# mcu.net
KiCad netlist of a schematic drawn in Altium Designer
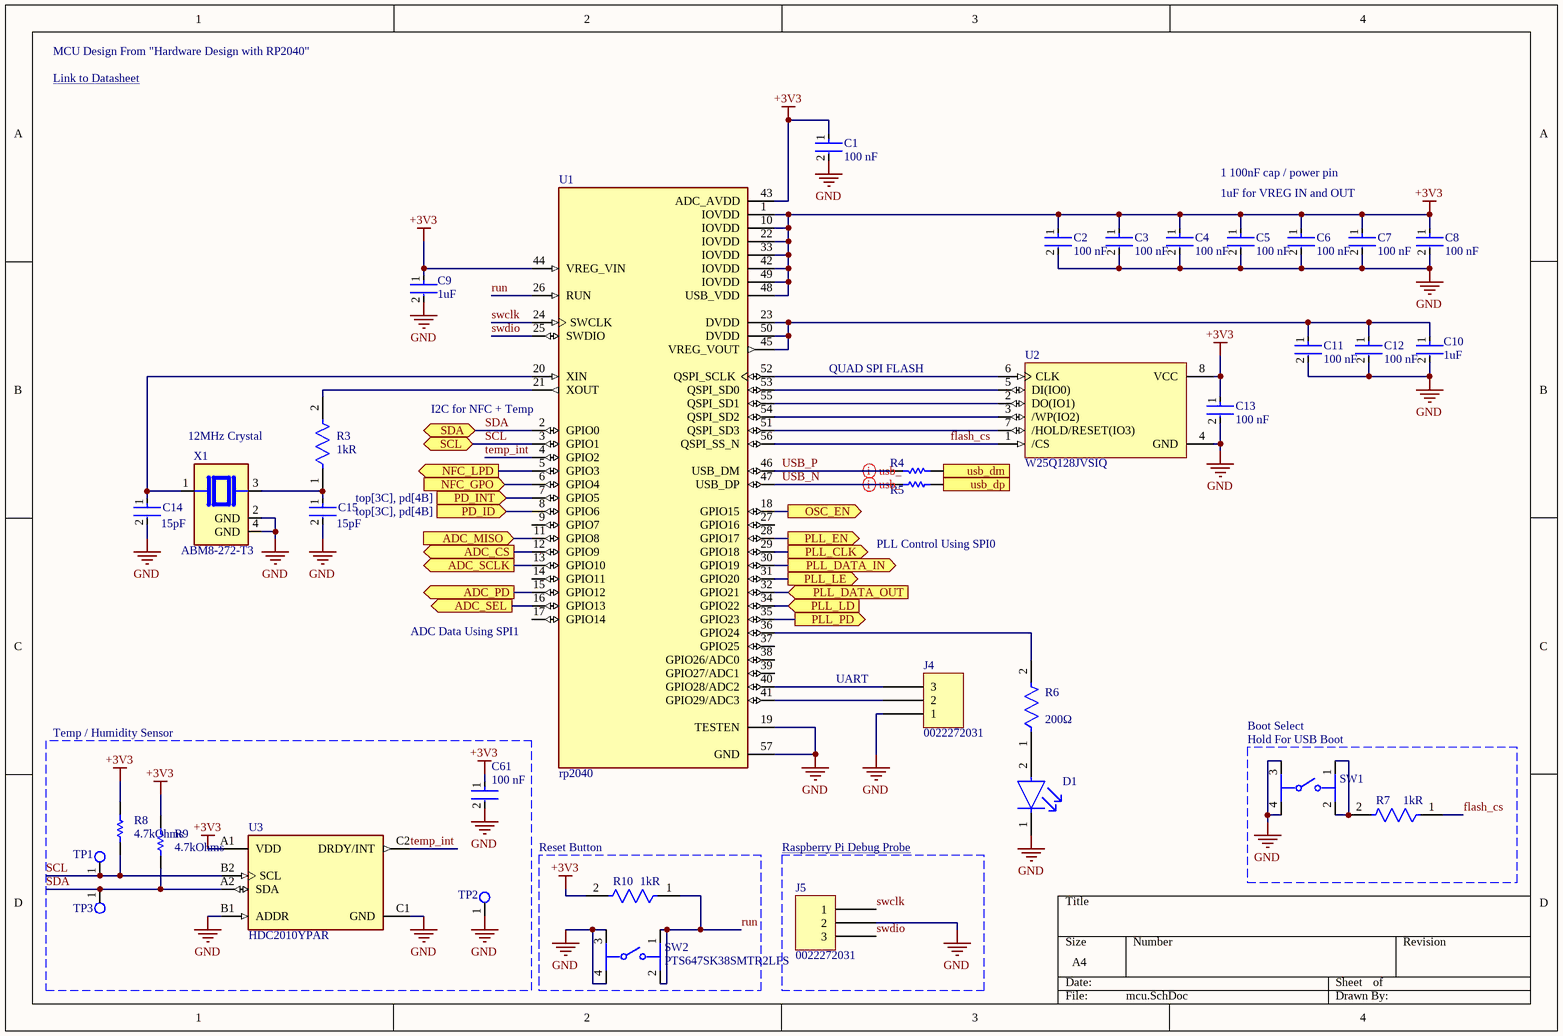
[diagram p0: mcu.SchDoc]

(export (version "E")
  (design (tool "Eeschema 10.0.6"))
  (components
    (comp (ref "C1")
      (value "CC0603KRX7R7BB104")
      (footprint "FP-CC0603-DA-MFG")
      (description "CAP CER 0.1UF 16V X7R 0603")
      (fields
        (field (name "OCTOPART") "https://octopart.com/cc0603krx7r7bb104-yageo-192941")
        (field (name "TOLERANCE") "0.1")
        (field (name "CAPACITANCE") "100 nF")
      )
      (libsource (lib "Altium Content Vault") (part "11868f565c42a9108669ba33697ecf6"))
    )
    (comp (ref "C2")
      (value "CC0603KRX7R7BB104")
      (footprint "FP-CC0603-DA-MFG")
      (description "CAP CER 0.1UF 16V X7R 0603")
      (fields
        (field (name "OCTOPART") "https://octopart.com/cc0603krx7r7bb104-yageo-192941")
        (field (name "TOLERANCE") "0.1")
        (field (name "CAPACITANCE") "100 nF")
      )
      (libsource (lib "Altium Content Vault") (part "11868f565c42a9108669ba33697ecf6"))
    )
    (comp (ref "C3")
      (value "CC0603KRX7R7BB104")
      (footprint "FP-CC0603-DA-MFG")
      (description "CAP CER 0.1UF 16V X7R 0603")
      (fields
        (field (name "OCTOPART") "https://octopart.com/cc0603krx7r7bb104-yageo-192941")
        (field (name "TOLERANCE") "0.1")
        (field (name "CAPACITANCE") "100 nF")
      )
      (libsource (lib "Altium Content Vault") (part "11868f565c42a9108669ba33697ecf6"))
    )
    (comp (ref "C4")
      (value "CC0603KRX7R7BB104")
      (footprint "FP-CC0603-DA-MFG")
      (description "CAP CER 0.1UF 16V X7R 0603")
      (fields
        (field (name "OCTOPART") "https://octopart.com/cc0603krx7r7bb104-yageo-192941")
        (field (name "TOLERANCE") "0.1")
        (field (name "CAPACITANCE") "100 nF")
      )
      (libsource (lib "Altium Content Vault") (part "11868f565c42a9108669ba33697ecf6"))
    )
    (comp (ref "C5")
      (value "CC0603KRX7R7BB104")
      (footprint "FP-CC0603-DA-MFG")
      (description "CAP CER 0.1UF 16V X7R 0603")
      (fields
        (field (name "OCTOPART") "https://octopart.com/cc0603krx7r7bb104-yageo-192941")
        (field (name "TOLERANCE") "0.1")
        (field (name "CAPACITANCE") "100 nF")
      )
      (libsource (lib "Altium Content Vault") (part "11868f565c42a9108669ba33697ecf6"))
    )
    (comp (ref "C6")
      (value "CC0603KRX7R7BB104")
      (footprint "FP-CC0603-DA-MFG")
      (description "CAP CER 0.1UF 16V X7R 0603")
      (fields
        (field (name "OCTOPART") "https://octopart.com/cc0603krx7r7bb104-yageo-192941")
        (field (name "TOLERANCE") "0.1")
        (field (name "CAPACITANCE") "100 nF")
      )
      (libsource (lib "Altium Content Vault") (part "11868f565c42a9108669ba33697ecf6"))
    )
    (comp (ref "C7")
      (value "CC0603KRX7R7BB104")
      (footprint "FP-CC0603-DA-MFG")
      (description "CAP CER 0.1UF 16V X7R 0603")
      (fields
        (field (name "OCTOPART") "https://octopart.com/cc0603krx7r7bb104-yageo-192941")
        (field (name "TOLERANCE") "0.1")
        (field (name "CAPACITANCE") "100 nF")
      )
      (libsource (lib "Altium Content Vault") (part "11868f565c42a9108669ba33697ecf6"))
    )
    (comp (ref "C8")
      (value "CC0603KRX7R7BB104")
      (footprint "FP-CC0603-DA-MFG")
      (description "CAP CER 0.1UF 16V X7R 0603")
      (fields
        (field (name "OCTOPART") "https://octopart.com/cc0603krx7r7bb104-yageo-192941")
        (field (name "TOLERANCE") "0.1")
        (field (name "CAPACITANCE") "100 nF")
      )
      (libsource (lib "Altium Content Vault") (part "11868f565c42a9108669ba33697ecf6"))
    )
    (comp (ref "C9")
      (value "CL10B105KP8NNNC")
      (footprint "FP-CL10-IPC_C")
      (description "Cap Ceramic 1uF 10V X7R ±10% Pad SMD 0603 +125°C T/R")
      (fields (field (name "CAPACITANCE") "1uF") (field (name "TOLERANCE") "10%"))
      (libsource (lib "Altium Content Vault") (part "b4654b650e69147ec39a6b967a45e02"))
    )
    (comp (ref "C10")
      (value "CL10B105KP8NNNC")
      (footprint "FP-CL10-IPC_C")
      (description "Cap Ceramic 1uF 10V X7R ±10% Pad SMD 0603 +125°C T/R")
      (fields (field (name "CAPACITANCE") "1uF") (field (name "TOLERANCE") "10%"))
      (libsource (lib "Altium Content Vault") (part "b4654b650e69147ec39a6b967a45e02"))
    )
    (comp (ref "C11")
      (value "CC0603KRX7R7BB104")
      (footprint "FP-CC0603-DA-MFG")
      (description "CAP CER 0.1UF 16V X7R 0603")
      (fields
        (field (name "OCTOPART") "https://octopart.com/cc0603krx7r7bb104-yageo-192941")
        (field (name "TOLERANCE") "0.1")
        (field (name "CAPACITANCE") "100 nF")
      )
      (libsource (lib "Altium Content Vault") (part "11868f565c42a9108669ba33697ecf6"))
    )
    (comp (ref "C12")
      (value "CC0603KRX7R7BB104")
      (footprint "FP-CC0603-DA-MFG")
      (description "CAP CER 0.1UF 16V X7R 0603")
      (fields
        (field (name "OCTOPART") "https://octopart.com/cc0603krx7r7bb104-yageo-192941")
        (field (name "TOLERANCE") "0.1")
        (field (name "CAPACITANCE") "100 nF")
      )
      (libsource (lib "Altium Content Vault") (part "11868f565c42a9108669ba33697ecf6"))
    )
    (comp (ref "C13")
      (value "CC0603KRX7R7BB104")
      (footprint "FP-CC0603-DA-MFG")
      (description "CAP CER 0.1UF 16V X7R 0603")
      (fields
        (field (name "OCTOPART") "https://octopart.com/cc0603krx7r7bb104-yageo-192941")
        (field (name "TOLERANCE") "0.1")
        (field (name "CAPACITANCE") "100 nF")
      )
      (libsource (lib "Altium Content Vault") (part "11868f565c42a9108669ba33697ecf6"))
    )
    (comp (ref "C14")
      (value "GJM1555C1H150GB01D")
      (footprint "FP-GJM155-0_05-MFG")
      (description "Multi-Layer Ceramic Capacitor 15pF C0G  ±2% 0402 Paper T/R")
      (fields (field (name "CAPACITANCE") "15pF") (field (name "TOLERANCE") "2%"))
      (libsource (lib "Altium Content Vault") (part "02cd4be3c70576c341d710602a673aa"))
    )
    (comp (ref "C15")
      (value "GJM1555C1H150GB01D")
      (footprint "FP-GJM155-0_05-MFG")
      (description "Multi-Layer Ceramic Capacitor 15pF C0G  ±2% 0402 Paper T/R")
      (fields (field (name "CAPACITANCE") "15pF") (field (name "TOLERANCE") "2%"))
      (libsource (lib "Altium Content Vault") (part "02cd4be3c70576c341d710602a673aa"))
    )
    (comp (ref "C61")
      (value "CC0603KRX7R7BB104")
      (footprint "FP-CC0603-DA-MFG")
      (description "CAP CER 0.1UF 16V X7R 0603")
      (fields
        (field (name "OCTOPART") "https://octopart.com/cc0603krx7r7bb104-yageo-192941")
        (field (name "TOLERANCE") "0.1")
        (field (name "CAPACITANCE") "100 nF")
      )
      (libsource (lib "Altium Content Vault") (part "11868f565c42a9108669ba33697ecf6"))
    )
    (comp (ref "D1")
      (value "LTST-C190KRKT")
      (footprint "FP-LTST-C190KRKT-MFG")
      (description "LED RED CLEAR CHIP SMD")
      (libsource (lib "Altium Content Vault") (part "8706943c75ba83719d021d2fdc84c58"))
    )
    (comp (ref "J4")
      (value "0022272031")
      (footprint "MOLEX KK 0022272031")
      (description "CONN HEADER VERT 3POS 2.54MM")
      (fields (field (name "MANUFACTURER") "Molex"))
      (libsource (lib "Celestial Altium Library - altium_library") (part "3 Pin"))
    )
    (comp (ref "J5")
      (value "0022272031")
      (footprint "MOLEX KK 0022272031")
      (description "CONN HEADER VERT 3POS 2.54MM")
      (fields (field (name "MANUFACTURER") "Molex"))
      (libsource (lib "") (part "3 Pin_1"))
    )
    (comp (ref "R3")
      (value "RC0603FR-071KL")
      (footprint "FP-RC0603-0_55-IPC_C")
      (description "RES 1K OHM 1% 1/10W 0603")
      (fields (field (name "RESISTANCE") "1kR") (field (name "TOLERANCE") "1%"))
      (libsource (lib "Altium Content Vault") (part "1029c3af85768c4190bb7ad29bc67b5"))
    )
    (comp (ref "R4")
      (value "RC0402JR-0727RL")
      (footprint "RESC1005X40X25NL05T10")
      (fields (field (name "MANUFACTURER") "Yageo / Phycomp"))
      (libsource (lib "Altium Content Vault") (part "RES"))
    )
    (comp (ref "R5")
      (value "RC0402JR-0727RL")
      (footprint "RESC1005X40X25NL05T10")
      (fields (field (name "MANUFACTURER") "Yageo / Phycomp"))
      (libsource (lib "Altium Content Vault") (part "RES"))
    )
    (comp (ref "R6")
      (value "200Ω")
      (footprint "FP-RT0402-MFG")
      (description "RES SMD 200 OHM 0.1% 1/16W 0402")
      (fields (field (name "TOLERANCE") "0.001") (field (name "MANUFACTURER PART NUMBER") "RT0402BRD07200RL"))
      (libsource (lib "Altium Content Vault") (part "1029c3af85768c4190bb7ad29bc67b5"))
    )
    (comp (ref "R7")
      (value "RC0603FR-071KL")
      (footprint "FP-RC0603-0_55-IPC_C")
      (description "RES 1K OHM 1% 1/10W 0603")
      (fields (field (name "RESISTANCE") "1kR") (field (name "TOLERANCE") "1%"))
      (libsource (lib "Altium Content Vault") (part "1029c3af85768c4190bb7ad29bc67b5"))
    )
    (comp (ref "R8")
      (value "RC0603FR-074K7L")
      (footprint "RESC1608X55X25LL10T15")
      (description "Chip Resistor, 4.7 KOhm, +/- 1%, 0.1 W, -55 to 155 degC, 0603 (1608 Metric), RoHS, Tape and Reel")
      (fields
        (field (name "MANUFACTURER") "Yageo")
        (field (name "RESISTANCE") "4.7kOhms")
        (field (name "TOLERANCE") "1%")
      )
      (libsource (lib "Altium Content Vault") (part "RES-2"))
    )
    (comp (ref "R9")
      (value "RC0603FR-074K7L")
      (footprint "RESC1608X55X25LL10T15")
      (description "Chip Resistor, 4.7 KOhm, +/- 1%, 0.1 W, -55 to 155 degC, 0603 (1608 Metric), RoHS, Tape and Reel")
      (fields
        (field (name "MANUFACTURER") "Yageo")
        (field (name "RESISTANCE") "4.7kOhms")
        (field (name "TOLERANCE") "1%")
      )
      (libsource (lib "Altium Content Vault") (part "RES-2"))
    )
    (comp (ref "R10")
      (value "RC0603FR-071KL")
      (footprint "FP-RC0603-0_55-IPC_C")
      (description "RES 1K OHM 1% 1/10W 0603")
      (fields (field (name "RESISTANCE") "1kR") (field (name "TOLERANCE") "1%"))
      (libsource (lib "Altium Content Vault") (part "1029c3af85768c4190bb7ad29bc67b5"))
    )
    (comp (ref "SW1")
      (value "PTS647SK38SMTR2LFS")
      (footprint "FP-PTS647SK38SMTR2LFS-MFG")
      (description "TACT 4.5 X 4.5, 3.8 MM H, 2.5N,")
      (libsource (lib "Altium Content Vault") (part "1adf0dd01260c80cf25a44bfd6b99ba"))
    )
    (comp (ref "SW2")
      (value "PTS647SK38SMTR2LFS")
      (footprint "FP-PTS647SK38SMTR2LFS-MFG")
      (description "TACT 4.5 X 4.5, 3.8 MM H, 2.5N,")
      (libsource (lib "Altium Content Vault") (part "1adf0dd01260c80cf25a44bfd6b99ba"))
    )
    (comp (ref "TP1")
      (value "Test Point")
      (footprint "test_point")
      (libsource (lib "fydp") (part "Test Point"))
    )
    (comp (ref "TP2")
      (value "Test Point")
      (footprint "test_point")
      (libsource (lib "fydp") (part "Test Point"))
    )
    (comp (ref "TP3")
      (value "Test Point")
      (footprint "test_point")
      (libsource (lib "fydp") (part "Test Point"))
    )
    (comp (ref "U1")
      (value "rp2040")
      (footprint "QFN40P700X700X90-57N")
      (libsource (lib "fydp") (part "rp2040"))
    )
    (comp (ref "U2")
      (value "W25Q128JVSIQ")
      (footprint "SOIC127P790X216-8N")
      (libsource (lib "fydp") (part "W25Q128JVSIQ"))
    )
    (comp (ref "U3")
      (value "HDC2010YPAR")
      (footprint "FP-YPA0006-MFG")
      (description "GEN 2 HUMIDITY SENSOR")
      (fields
        (field (name "MANUFACTURER") "Texas Instruments")
        (field (name "OCTOPART") "https://octopart.com/hdc2010ypar-texas+instruments-84791680")
      )
      (libsource (lib "Altium Content Vault") (part "89629a78d3446019ed046f2f7a99f7b"))
    )
    (comp (ref "X1")
      (value "ABM8-272-T3")
      (footprint "XTAL_ABM8-272-T3")
      (libsource (lib "fydp") (part "ABM8-272-T3"))
    )
  )
  (nets
    (net (code "1") (name "+3V3") (class "Default")
      (node (ref "C1") (pin "1") (pinfunction "1_1") (pintype "passive"))
      (node (ref "C13") (pin "1") (pinfunction "1_1") (pintype "passive"))
      (node (ref "C2") (pin "1") (pinfunction "1_1") (pintype "passive"))
      (node (ref "C3") (pin "1") (pinfunction "1_1") (pintype "passive"))
      (node (ref "C4") (pin "1") (pinfunction "1_1") (pintype "passive"))
      (node (ref "C5") (pin "1") (pinfunction "1_1") (pintype "passive"))
      (node (ref "C6") (pin "1") (pinfunction "1_1") (pintype "passive"))
      (node (ref "C61") (pin "1") (pinfunction "1_1") (pintype "passive"))
      (node (ref "C7") (pin "1") (pinfunction "1_1") (pintype "passive"))
      (node (ref "C8") (pin "1") (pinfunction "1_1") (pintype "passive"))
      (node (ref "C9") (pin "1") (pinfunction "1_1") (pintype "passive"))
      (node (ref "R10") (pin "2") (pinfunction "2_2") (pintype "passive"))
      (node (ref "R8") (pin "2") (pinfunction "2_2") (pintype "passive"))
      (node (ref "R9") (pin "2") (pinfunction "2_2") (pintype "passive"))
      (node (ref "U1") (pin "1") (pinfunction "IOVDD_1") (pintype "power_in"))
      (node (ref "U1") (pin "10") (pinfunction "IOVDD_10") (pintype "power_in"))
      (node (ref "U1") (pin "22") (pinfunction "IOVDD_22") (pintype "power_in"))
      (node (ref "U1") (pin "33") (pinfunction "IOVDD_33") (pintype "power_in"))
      (node (ref "U1") (pin "42") (pinfunction "IOVDD_42") (pintype "power_in"))
      (node (ref "U1") (pin "43") (pinfunction "ADC_AVDD_43") (pintype "power_in"))
      (node (ref "U1") (pin "44") (pinfunction "VREG_VIN_44") (pintype "input"))
      (node (ref "U1") (pin "48") (pinfunction "USB_VDD_48") (pintype "power_in"))
      (node (ref "U1") (pin "49") (pinfunction "IOVDD_49") (pintype "power_in"))
      (node (ref "U2") (pin "8") (pinfunction "VCC_8") (pintype "power_in"))
      (node (ref "U3") (pin "A1") (pinfunction "VDD_A1") (pintype "power_in"))
    )
    (net (code "2") (name "/ADC_CS") (class "Default")
      (node (ref "U1") (pin "12") (pinfunction "GPIO9_12") (pintype "bidirectional"))
    )
    (net (code "3") (name "/ADC_MISO") (class "Default")
      (node (ref "U1") (pin "11") (pinfunction "GPIO8_11") (pintype "bidirectional"))
    )
    (net (code "4") (name "/ADC_PD") (class "Default")
      (node (ref "U1") (pin "15") (pinfunction "GPIO12_15") (pintype "bidirectional"))
    )
    (net (code "5") (name "/ADC_SCLK") (class "Default")
      (node (ref "U1") (pin "13") (pinfunction "GPIO10_13") (pintype "bidirectional"))
    )
    (net (code "6") (name "/ADC_SEL") (class "Default")
      (node (ref "U1") (pin "16") (pinfunction "GPIO13_16") (pintype "bidirectional"))
    )
    (net (code "7") (name "/NFC_GPO") (class "Default")
      (node (ref "U1") (pin "6") (pinfunction "GPIO4_6") (pintype "bidirectional"))
    )
    (net (code "8") (name "/NFC_LPD") (class "Default")
      (node (ref "U1") (pin "5") (pinfunction "GPIO3_5") (pintype "bidirectional"))
    )
    (net (code "9") (name "/OSC_EN") (class "Default")
      (node (ref "U1") (pin "18") (pinfunction "GPIO15_18") (pintype "bidirectional"))
    )
    (net (code "10") (name "/PD_ID") (class "Default")
      (node (ref "U1") (pin "8") (pinfunction "GPIO6_8") (pintype "bidirectional"))
    )
    (net (code "11") (name "/PD_INT") (class "Default")
      (node (ref "U1") (pin "7") (pinfunction "GPIO5_7") (pintype "bidirectional"))
    )
    (net (code "12") (name "/PLL_CLK") (class "Default")
      (node (ref "U1") (pin "29") (pinfunction "GPIO18_29") (pintype "bidirectional"))
    )
    (net (code "13") (name "/PLL_DATA_IN") (class "Default")
      (node (ref "U1") (pin "30") (pinfunction "GPIO19_30") (pintype "bidirectional"))
    )
    (net (code "14") (name "/PLL_DATA_OUT") (class "Default")
      (node (ref "U1") (pin "32") (pinfunction "GPIO21_32") (pintype "bidirectional"))
    )
    (net (code "15") (name "/PLL_EN") (class "Default")
      (node (ref "U1") (pin "28") (pinfunction "GPIO17_28") (pintype "bidirectional"))
    )
    (net (code "16") (name "/PLL_LD") (class "Default")
      (node (ref "U1") (pin "34") (pinfunction "GPIO22_34") (pintype "bidirectional"))
    )
    (net (code "17") (name "/PLL_LE") (class "Default")
      (node (ref "U1") (pin "31") (pinfunction "GPIO20_31") (pintype "bidirectional"))
    )
    (net (code "18") (name "/PLL_PD") (class "Default")
      (node (ref "U1") (pin "35") (pinfunction "GPIO23_35") (pintype "bidirectional"))
    )
    (net (code "19") (name "/SCL") (class "Default")
      (node (ref "R8") (pin "1") (pinfunction "1_1") (pintype "passive"))
      (node (ref "TP1") (pin "1") (pintype "passive"))
      (node (ref "U1") (pin "3") (pinfunction "GPIO1_3") (pintype "bidirectional"))
      (node (ref "U3") (pin "B2") (pinfunction "SCL_B2") (pintype "input"))
    )
    (net (code "20") (name "/SDA") (class "Default")
      (node (ref "R9") (pin "1") (pinfunction "1_1") (pintype "passive"))
      (node (ref "TP3") (pin "1") (pintype "passive"))
      (node (ref "U1") (pin "2") (pinfunction "GPIO0_2") (pintype "bidirectional"))
      (node (ref "U3") (pin "A2") (pinfunction "SDA_A2") (pintype "bidirectional"))
    )
    (net (code "21") (name "/USB_N") (class "Default")
      (node (ref "R5") (pin "1") (pinfunction "1_1") (pintype "passive"))
      (node (ref "U1") (pin "47") (pinfunction "USB_DP_47") (pintype "bidirectional"))
    )
    (net (code "22") (name "/USB_P") (class "Default")
      (node (ref "R4") (pin "1") (pinfunction "1_1") (pintype "passive"))
      (node (ref "U1") (pin "46") (pinfunction "USB_DM_46") (pintype "bidirectional"))
    )
    (net (code "23") (name "/flash_cs") (class "Default")
      (node (ref "R7") (pin "1") (pinfunction "1_1") (pintype "passive"))
      (node (ref "U1") (pin "56") (pinfunction "QSPI_SS_N_56") (pintype "bidirectional"))
      (node (ref "U2") (pin "1") (pinfunction "/CS_1") (pintype "input"))
    )
    (net (code "24") (name "/run") (class "Default")
      (node (ref "R10") (pin "1") (pinfunction "1_1") (pintype "passive"))
      (node (ref "SW2") (pin "1") (pinfunction "1_1") (pintype "passive"))
      (node (ref "SW2") (pin "2") (pinfunction "2_2") (pintype "passive"))
      (node (ref "U1") (pin "26") (pinfunction "RUN_26") (pintype "input"))
    )
    (net (code "25") (name "/swclk") (class "Default")
      (node (ref "J5") (pin "1") (pinfunction "1_1") (pintype "passive"))
      (node (ref "U1") (pin "24") (pinfunction "SWCLK_24") (pintype "input"))
    )
    (net (code "26") (name "/swdio") (class "Default")
      (node (ref "J5") (pin "3") (pinfunction "3_3") (pintype "passive"))
      (node (ref "U1") (pin "25") (pinfunction "SWDIO_25") (pintype "bidirectional"))
    )
    (net (code "27") (name "/temp_int") (class "Default")
      (node (ref "U1") (pin "4") (pinfunction "GPIO2_4") (pintype "bidirectional"))
      (node (ref "U3") (pin "C2") (pinfunction "DRDY/INT_C2") (pintype "output"))
    )
    (net (code "28") (name "/usb_dm") (class "Default")
      (node (ref "R4") (pin "2") (pinfunction "2_2") (pintype "passive"))
    )
    (net (code "29") (name "/usb_dp") (class "Default")
      (node (ref "R5") (pin "2") (pinfunction "2_2") (pintype "passive"))
    )
    (net (code "30") (name "GND") (class "Default")
      (node (ref "C1") (pin "2") (pinfunction "2_2") (pintype "passive"))
      (node (ref "C10") (pin "2") (pinfunction "2_2") (pintype "passive"))
      (node (ref "C11") (pin "2") (pinfunction "2_2") (pintype "passive"))
      (node (ref "C12") (pin "2") (pinfunction "2_2") (pintype "passive"))
      (node (ref "C13") (pin "2") (pinfunction "2_2") (pintype "passive"))
      (node (ref "C14") (pin "2") (pinfunction "2_2") (pintype "passive"))
      (node (ref "C15") (pin "2") (pinfunction "2_2") (pintype "passive"))
      (node (ref "C2") (pin "2") (pinfunction "2_2") (pintype "passive"))
      (node (ref "C3") (pin "2") (pinfunction "2_2") (pintype "passive"))
      (node (ref "C4") (pin "2") (pinfunction "2_2") (pintype "passive"))
      (node (ref "C5") (pin "2") (pinfunction "2_2") (pintype "passive"))
      (node (ref "C6") (pin "2") (pinfunction "2_2") (pintype "passive"))
      (node (ref "C61") (pin "2") (pinfunction "2_2") (pintype "passive"))
      (node (ref "C7") (pin "2") (pinfunction "2_2") (pintype "passive"))
      (node (ref "C8") (pin "2") (pinfunction "2_2") (pintype "passive"))
      (node (ref "C9") (pin "2") (pinfunction "2_2") (pintype "passive"))
      (node (ref "D1") (pin "1") (pinfunction "C_1") (pintype "passive"))
      (node (ref "J4") (pin "1") (pinfunction "1_1") (pintype "passive"))
      (node (ref "J5") (pin "2") (pinfunction "2_2") (pintype "passive"))
      (node (ref "SW1") (pin "3") (pinfunction "3_3") (pintype "passive"))
      (node (ref "SW1") (pin "4") (pinfunction "4_4") (pintype "passive"))
      (node (ref "SW2") (pin "3") (pinfunction "3_3") (pintype "passive"))
      (node (ref "SW2") (pin "4") (pinfunction "4_4") (pintype "passive"))
      (node (ref "TP2") (pin "1") (pintype "passive"))
      (node (ref "U1") (pin "19") (pinfunction "TESTEN_19") (pintype "passive"))
      (node (ref "U1") (pin "57") (pinfunction "GND_57") (pintype "power_in"))
      (node (ref "U2") (pin "4") (pinfunction "GND_4") (pintype "power_in"))
      (node (ref "U3") (pin "B1") (pinfunction "ADDR_B1") (pintype "input"))
      (node (ref "U3") (pin "C1") (pinfunction "GND_C1") (pintype "power_in"))
      (node (ref "X1") (pin "2") (pinfunction "GND_2") (pintype "power_in"))
      (node (ref "X1") (pin "4") (pinfunction "GND_4") (pintype "power_in"))
    )
    (net (code "31") (name "Net-(C15-Pad1)") (class "Default")
      (node (ref "C15") (pin "1") (pinfunction "1_1") (pintype "passive"))
      (node (ref "R3") (pin "1") (pinfunction "1_1") (pintype "passive"))
      (node (ref "X1") (pin "3") (pinfunction "3_3") (pintype "passive"))
    )
    (net (code "32") (name "Net-(D1-A)") (class "Default")
      (node (ref "D1") (pin "2") (pinfunction "A_2") (pintype "passive"))
      (node (ref "R6") (pin "1") (pinfunction "1_1") (pintype "passive"))
    )
    (net (code "33") (name "Net-(R7-Pad2)") (class "Default")
      (node (ref "R7") (pin "2") (pinfunction "2_2") (pintype "passive"))
      (node (ref "SW1") (pin "1") (pinfunction "1_1") (pintype "passive"))
      (node (ref "SW1") (pin "2") (pinfunction "2_2") (pintype "passive"))
    )
    (net (code "34") (name "Net-(U1-GPIO24)") (class "Default")
      (node (ref "R6") (pin "2") (pinfunction "2_2") (pintype "passive"))
      (node (ref "U1") (pin "36") (pinfunction "GPIO24_36") (pintype "bidirectional"))
    )
    (net (code "35") (name "Net-(U1-GPIO28{slash}ADC2)") (class "Default")
      (node (ref "J4") (pin "3") (pinfunction "3_3") (pintype "passive"))
      (node (ref "U1") (pin "40") (pinfunction "GPIO28/ADC2_40") (pintype "bidirectional"))
    )
    (net (code "36") (name "Net-(U1-GPIO29{slash}ADC3)") (class "Default")
      (node (ref "J4") (pin "2") (pinfunction "2_2") (pintype "passive"))
      (node (ref "U1") (pin "41") (pinfunction "GPIO29/ADC3_41") (pintype "bidirectional"))
    )
    (net (code "37") (name "Net-(U1-QSPI_SCLK)") (class "Default")
      (node (ref "U1") (pin "52") (pinfunction "QSPI_SCLK_52") (pintype "bidirectional"))
      (node (ref "U2") (pin "6") (pinfunction "CLK_6") (pintype "input"))
    )
    (net (code "38") (name "Net-(U1-QSPI_SD0)") (class "Default")
      (node (ref "U1") (pin "53") (pinfunction "QSPI_SD0_53") (pintype "bidirectional"))
      (node (ref "U2") (pin "5") (pinfunction "DI(IO0)_5") (pintype "bidirectional"))
    )
    (net (code "39") (name "Net-(U1-QSPI_SD1)") (class "Default")
      (node (ref "U1") (pin "55") (pinfunction "QSPI_SD1_55") (pintype "bidirectional"))
      (node (ref "U2") (pin "2") (pinfunction "DO(IO1)_2") (pintype "bidirectional"))
    )
    (net (code "40") (name "Net-(U1-QSPI_SD2)") (class "Default")
      (node (ref "U1") (pin "54") (pinfunction "QSPI_SD2_54") (pintype "bidirectional"))
      (node (ref "U2") (pin "3") (pinfunction "/WP(IO2)_3") (pintype "bidirectional"))
    )
    (net (code "41") (name "Net-(U1-QSPI_SD3)") (class "Default")
      (node (ref "U1") (pin "51") (pinfunction "QSPI_SD3_51") (pintype "bidirectional"))
      (node (ref "U2") (pin "7") (pinfunction "/HOLD/RESET(IO3)_7") (pintype "bidirectional"))
    )
    (net (code "42") (name "Net-(U1-VREG_VOUT)") (class "Default")
      (node (ref "C10") (pin "1") (pinfunction "1_1") (pintype "passive"))
      (node (ref "C11") (pin "1") (pinfunction "1_1") (pintype "passive"))
      (node (ref "C12") (pin "1") (pinfunction "1_1") (pintype "passive"))
      (node (ref "U1") (pin "23") (pinfunction "DVDD_23") (pintype "power_in"))
      (node (ref "U1") (pin "45") (pinfunction "VREG_VOUT_45") (pintype "output"))
      (node (ref "U1") (pin "50") (pinfunction "DVDD_50") (pintype "power_in"))
    )
    (net (code "43") (name "Net-(U1-XIN)") (class "Default")
      (node (ref "C14") (pin "1") (pinfunction "1_1") (pintype "passive"))
      (node (ref "U1") (pin "20") (pinfunction "XIN_20") (pintype "input"))
      (node (ref "X1") (pin "1") (pinfunction "1_1") (pintype "passive"))
    )
    (net (code "44") (name "Net-(U1-XOUT)") (class "Default")
      (node (ref "R3") (pin "2") (pinfunction "2_2") (pintype "passive"))
      (node (ref "U1") (pin "21") (pinfunction "XOUT_21") (pintype "output"))
    )
    (net (code "45") (name "unconnected-(U1-GPIO7-Pad9)") (class "Default")
      (node (ref "U1") (pin "9") (pinfunction "GPIO7_9") (pintype "bidirectional"))
    )
    (net (code "46") (name "unconnected-(U1-GPIO11-Pad14)") (class "Default")
      (node (ref "U1") (pin "14") (pinfunction "GPIO11_14") (pintype "bidirectional"))
    )
    (net (code "47") (name "unconnected-(U1-GPIO14-Pad17)") (class "Default")
      (node (ref "U1") (pin "17") (pinfunction "GPIO14_17") (pintype "bidirectional"))
    )
    (net (code "48") (name "unconnected-(U1-GPIO16-Pad27)") (class "Default")
      (node (ref "U1") (pin "27") (pinfunction "GPIO16_27") (pintype "bidirectional"))
    )
    (net (code "49") (name "unconnected-(U1-GPIO25-Pad37)") (class "Default")
      (node (ref "U1") (pin "37") (pinfunction "GPIO25_37") (pintype "bidirectional"))
    )
    (net (code "50") (name "unconnected-(U1-GPIO26{slash}ADC0-Pad38)") (class "Default")
      (node (ref "U1") (pin "38") (pinfunction "GPIO26/ADC0_38") (pintype "bidirectional"))
    )
    (net (code "51") (name "unconnected-(U1-GPIO27{slash}ADC1-Pad39)") (class "Default")
      (node (ref "U1") (pin "39") (pinfunction "GPIO27/ADC1_39") (pintype "bidirectional"))
    )
  )
)
